# TinyCube11b_Lib.net
KiCad netlist of a schematic drawn in EAGLE
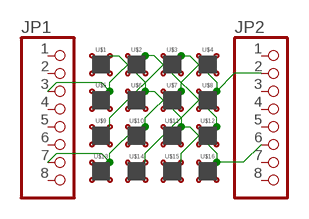
[diagram p0: schematic, sheet 1]

(export (version "E")
  (design (tool "Eeschema 10.0.6"))
  (components
    (comp (ref "JP1")
      (value "PINHD-1X8BIG")
      (footprint "eagle-import:1X08-BIG")
      (libsource (lib "eagle-import") (part "PINHD-1X8BIG"))
    )
    (comp (ref "JP2")
      (value "PINHD-1X8BIG")
      (footprint "eagle-import:1X08-BIG")
      (libsource (lib "eagle-import") (part "PINHD-1X8BIG"))
    )
    (comp (ref "U$1")
      (value "PILLAR")
      (footprint "eagle-import:10MIL")
      (libsource (lib "eagle-import") (part "PILLAR"))
    )
    (comp (ref "U$2")
      (value "PILLAR")
      (footprint "eagle-import:10MIL")
      (libsource (lib "eagle-import") (part "PILLAR"))
    )
    (comp (ref "U$3")
      (value "PILLAR")
      (footprint "eagle-import:10MIL")
      (libsource (lib "eagle-import") (part "PILLAR"))
    )
    (comp (ref "U$4")
      (value "PILLAR")
      (footprint "eagle-import:10MIL")
      (libsource (lib "eagle-import") (part "PILLAR"))
    )
    (comp (ref "U$5")
      (value "PILLAR")
      (footprint "eagle-import:10MIL")
      (libsource (lib "eagle-import") (part "PILLAR"))
    )
    (comp (ref "U$6")
      (value "PILLAR")
      (footprint "eagle-import:10MIL")
      (libsource (lib "eagle-import") (part "PILLAR"))
    )
    (comp (ref "U$7")
      (value "PILLAR")
      (footprint "eagle-import:10MIL")
      (libsource (lib "eagle-import") (part "PILLAR"))
    )
    (comp (ref "U$8")
      (value "PILLAR")
      (footprint "eagle-import:10MIL")
      (libsource (lib "eagle-import") (part "PILLAR"))
    )
    (comp (ref "U$9")
      (value "PILLAR")
      (footprint "eagle-import:10MIL")
      (libsource (lib "eagle-import") (part "PILLAR"))
    )
    (comp (ref "U$10")
      (value "PILLAR")
      (footprint "eagle-import:10MIL")
      (libsource (lib "eagle-import") (part "PILLAR"))
    )
    (comp (ref "U$11")
      (value "PILLAR")
      (footprint "eagle-import:10MIL")
      (libsource (lib "eagle-import") (part "PILLAR"))
    )
    (comp (ref "U$12")
      (value "PILLAR")
      (footprint "eagle-import:10MIL")
      (libsource (lib "eagle-import") (part "PILLAR"))
    )
    (comp (ref "U$13")
      (value "PILLAR")
      (footprint "eagle-import:10MIL")
      (libsource (lib "eagle-import") (part "PILLAR"))
    )
    (comp (ref "U$14")
      (value "PILLAR")
      (footprint "eagle-import:10MIL")
      (libsource (lib "eagle-import") (part "PILLAR"))
    )
    (comp (ref "U$15")
      (value "PILLAR")
      (footprint "eagle-import:10MIL")
      (libsource (lib "eagle-import") (part "PILLAR"))
    )
    (comp (ref "U$16")
      (value "PILLAR")
      (footprint "eagle-import:10MIL")
      (libsource (lib "eagle-import") (part "PILLAR"))
    )
  )
  (nets
    (net (code "1") (name "Net-(U$1-G)") (class "Default")
      (node (ref "JP2") (pin "6") (pinfunction "6_6") (pintype "passive"))
      (node (ref "U$1") (pin "+") (pinfunction "G_+") (pintype "bidirectional"))
      (node (ref "U$11") (pin "+") (pinfunction "G_+") (pintype "bidirectional"))
      (node (ref "U$16") (pin "+") (pinfunction "G_+") (pintype "bidirectional"))
      (node (ref "U$6") (pin "+") (pinfunction "G_+") (pintype "bidirectional"))
    )
    (net (code "2") (name "Net-(U$10-G)") (class "Default")
      (node (ref "JP1") (pin "7") (pinfunction "7_7") (pintype "passive"))
      (node (ref "U$10") (pin "+") (pinfunction "G_+") (pintype "bidirectional"))
      (node (ref "U$13") (pin "+") (pinfunction "G_+") (pintype "bidirectional"))
      (node (ref "U$4") (pin "+") (pinfunction "G_+") (pintype "bidirectional"))
      (node (ref "U$7") (pin "+") (pinfunction "G_+") (pintype "bidirectional"))
    )
    (net (code "3") (name "Net-(U$12-G)") (class "Default")
      (node (ref "JP1") (pin "3") (pinfunction "3_3") (pintype "passive"))
      (node (ref "U$12") (pin "+") (pinfunction "G_+") (pintype "bidirectional"))
      (node (ref "U$15") (pin "+") (pinfunction "G_+") (pintype "bidirectional"))
      (node (ref "U$2") (pin "+") (pinfunction "G_+") (pintype "bidirectional"))
      (node (ref "U$5") (pin "+") (pinfunction "G_+") (pintype "bidirectional"))
    )
    (net (code "4") (name "Net-(U$14-G)") (class "Default")
      (node (ref "JP2") (pin "2") (pinfunction "2_2") (pintype "passive"))
      (node (ref "U$14") (pin "+") (pinfunction "G_+") (pintype "bidirectional"))
      (node (ref "U$3") (pin "+") (pinfunction "G_+") (pintype "bidirectional"))
      (node (ref "U$8") (pin "+") (pinfunction "G_+") (pintype "bidirectional"))
      (node (ref "U$9") (pin "+") (pinfunction "G_+") (pintype "bidirectional"))
    )
    (net (code "5") (name "unconnected-(JP1-Pad1)") (class "Default")
      (node (ref "JP1") (pin "1") (pinfunction "1_1") (pintype "passive"))
    )
    (net (code "6") (name "unconnected-(JP1-Pad2)") (class "Default")
      (node (ref "JP1") (pin "2") (pinfunction "2_2") (pintype "passive"))
    )
    (net (code "7") (name "unconnected-(JP1-Pad4)") (class "Default")
      (node (ref "JP1") (pin "4") (pinfunction "4_4") (pintype "passive"))
    )
    (net (code "8") (name "unconnected-(JP1-Pad5)") (class "Default")
      (node (ref "JP1") (pin "5") (pinfunction "5_5") (pintype "passive"))
    )
    (net (code "9") (name "unconnected-(JP1-Pad6)") (class "Default")
      (node (ref "JP1") (pin "6") (pinfunction "6_6") (pintype "passive"))
    )
    (net (code "10") (name "unconnected-(JP1-Pad8)") (class "Default")
      (node (ref "JP1") (pin "8") (pinfunction "8_8") (pintype "passive"))
    )
    (net (code "11") (name "unconnected-(JP2-Pad1)") (class "Default")
      (node (ref "JP2") (pin "1") (pinfunction "1_1") (pintype "passive"))
    )
    (net (code "12") (name "unconnected-(JP2-Pad3)") (class "Default")
      (node (ref "JP2") (pin "3") (pinfunction "3_3") (pintype "passive"))
    )
    (net (code "13") (name "unconnected-(JP2-Pad4)") (class "Default")
      (node (ref "JP2") (pin "4") (pinfunction "4_4") (pintype "passive"))
    )
    (net (code "14") (name "unconnected-(JP2-Pad5)") (class "Default")
      (node (ref "JP2") (pin "5") (pinfunction "5_5") (pintype "passive"))
    )
    (net (code "15") (name "unconnected-(JP2-Pad7)") (class "Default")
      (node (ref "JP2") (pin "7") (pinfunction "7_7") (pintype "passive"))
    )
    (net (code "16") (name "unconnected-(JP2-Pad8)") (class "Default")
      (node (ref "JP2") (pin "8") (pinfunction "8_8") (pintype "passive"))
    )
    (net (code "17") (name "unconnected-(U$1-A-PadG)") (class "Default")
      (node (ref "U$1") (pin "G") (pinfunction "A_G") (pintype "bidirectional"))
    )
    (net (code "18") (name "unconnected-(U$1-B-PadR)") (class "Default")
      (node (ref "U$1") (pin "R") (pinfunction "B_R") (pintype "bidirectional"))
    )
    (net (code "19") (name "unconnected-(U$1-R-PadB)") (class "Default")
      (node (ref "U$1") (pin "B") (pinfunction "R_B") (pintype "bidirectional"))
    )
    (net (code "20") (name "unconnected-(U$2-A-PadG)") (class "Default")
      (node (ref "U$2") (pin "G") (pinfunction "A_G") (pintype "bidirectional"))
    )
    (net (code "21") (name "unconnected-(U$2-B-PadR)") (class "Default")
      (node (ref "U$2") (pin "R") (pinfunction "B_R") (pintype "bidirectional"))
    )
    (net (code "22") (name "unconnected-(U$2-R-PadB)") (class "Default")
      (node (ref "U$2") (pin "B") (pinfunction "R_B") (pintype "bidirectional"))
    )
    (net (code "23") (name "unconnected-(U$3-A-PadG)") (class "Default")
      (node (ref "U$3") (pin "G") (pinfunction "A_G") (pintype "bidirectional"))
    )
    (net (code "24") (name "unconnected-(U$3-B-PadR)") (class "Default")
      (node (ref "U$3") (pin "R") (pinfunction "B_R") (pintype "bidirectional"))
    )
    (net (code "25") (name "unconnected-(U$3-R-PadB)") (class "Default")
      (node (ref "U$3") (pin "B") (pinfunction "R_B") (pintype "bidirectional"))
    )
    (net (code "26") (name "unconnected-(U$4-A-PadG)") (class "Default")
      (node (ref "U$4") (pin "G") (pinfunction "A_G") (pintype "bidirectional"))
    )
    (net (code "27") (name "unconnected-(U$4-B-PadR)") (class "Default")
      (node (ref "U$4") (pin "R") (pinfunction "B_R") (pintype "bidirectional"))
    )
    (net (code "28") (name "unconnected-(U$4-R-PadB)") (class "Default")
      (node (ref "U$4") (pin "B") (pinfunction "R_B") (pintype "bidirectional"))
    )
    (net (code "29") (name "unconnected-(U$5-A-PadG)") (class "Default")
      (node (ref "U$5") (pin "G") (pinfunction "A_G") (pintype "bidirectional"))
    )
    (net (code "30") (name "unconnected-(U$5-B-PadR)") (class "Default")
      (node (ref "U$5") (pin "R") (pinfunction "B_R") (pintype "bidirectional"))
    )
    (net (code "31") (name "unconnected-(U$5-R-PadB)") (class "Default")
      (node (ref "U$5") (pin "B") (pinfunction "R_B") (pintype "bidirectional"))
    )
    (net (code "32") (name "unconnected-(U$6-A-PadG)") (class "Default")
      (node (ref "U$6") (pin "G") (pinfunction "A_G") (pintype "bidirectional"))
    )
    (net (code "33") (name "unconnected-(U$6-B-PadR)") (class "Default")
      (node (ref "U$6") (pin "R") (pinfunction "B_R") (pintype "bidirectional"))
    )
    (net (code "34") (name "unconnected-(U$6-R-PadB)") (class "Default")
      (node (ref "U$6") (pin "B") (pinfunction "R_B") (pintype "bidirectional"))
    )
    (net (code "35") (name "unconnected-(U$7-A-PadG)") (class "Default")
      (node (ref "U$7") (pin "G") (pinfunction "A_G") (pintype "bidirectional"))
    )
    (net (code "36") (name "unconnected-(U$7-B-PadR)") (class "Default")
      (node (ref "U$7") (pin "R") (pinfunction "B_R") (pintype "bidirectional"))
    )
    (net (code "37") (name "unconnected-(U$7-R-PadB)") (class "Default")
      (node (ref "U$7") (pin "B") (pinfunction "R_B") (pintype "bidirectional"))
    )
    (net (code "38") (name "unconnected-(U$8-A-PadG)") (class "Default")
      (node (ref "U$8") (pin "G") (pinfunction "A_G") (pintype "bidirectional"))
    )
    (net (code "39") (name "unconnected-(U$8-B-PadR)") (class "Default")
      (node (ref "U$8") (pin "R") (pinfunction "B_R") (pintype "bidirectional"))
    )
    (net (code "40") (name "unconnected-(U$8-R-PadB)") (class "Default")
      (node (ref "U$8") (pin "B") (pinfunction "R_B") (pintype "bidirectional"))
    )
    (net (code "41") (name "unconnected-(U$9-A-PadG)") (class "Default")
      (node (ref "U$9") (pin "G") (pinfunction "A_G") (pintype "bidirectional"))
    )
    (net (code "42") (name "unconnected-(U$9-B-PadR)") (class "Default")
      (node (ref "U$9") (pin "R") (pinfunction "B_R") (pintype "bidirectional"))
    )
    (net (code "43") (name "unconnected-(U$9-R-PadB)") (class "Default")
      (node (ref "U$9") (pin "B") (pinfunction "R_B") (pintype "bidirectional"))
    )
    (net (code "44") (name "unconnected-(U$10-A-PadG)") (class "Default")
      (node (ref "U$10") (pin "G") (pinfunction "A_G") (pintype "bidirectional"))
    )
    (net (code "45") (name "unconnected-(U$10-B-PadR)") (class "Default")
      (node (ref "U$10") (pin "R") (pinfunction "B_R") (pintype "bidirectional"))
    )
    (net (code "46") (name "unconnected-(U$10-R-PadB)") (class "Default")
      (node (ref "U$10") (pin "B") (pinfunction "R_B") (pintype "bidirectional"))
    )
    (net (code "47") (name "unconnected-(U$11-A-PadG)") (class "Default")
      (node (ref "U$11") (pin "G") (pinfunction "A_G") (pintype "bidirectional"))
    )
    (net (code "48") (name "unconnected-(U$11-B-PadR)") (class "Default")
      (node (ref "U$11") (pin "R") (pinfunction "B_R") (pintype "bidirectional"))
    )
    (net (code "49") (name "unconnected-(U$11-R-PadB)") (class "Default")
      (node (ref "U$11") (pin "B") (pinfunction "R_B") (pintype "bidirectional"))
    )
    (net (code "50") (name "unconnected-(U$12-A-PadG)") (class "Default")
      (node (ref "U$12") (pin "G") (pinfunction "A_G") (pintype "bidirectional"))
    )
    (net (code "51") (name "unconnected-(U$12-B-PadR)") (class "Default")
      (node (ref "U$12") (pin "R") (pinfunction "B_R") (pintype "bidirectional"))
    )
    (net (code "52") (name "unconnected-(U$12-R-PadB)") (class "Default")
      (node (ref "U$12") (pin "B") (pinfunction "R_B") (pintype "bidirectional"))
    )
    (net (code "53") (name "unconnected-(U$13-A-PadG)") (class "Default")
      (node (ref "U$13") (pin "G") (pinfunction "A_G") (pintype "bidirectional"))
    )
    (net (code "54") (name "unconnected-(U$13-B-PadR)") (class "Default")
      (node (ref "U$13") (pin "R") (pinfunction "B_R") (pintype "bidirectional"))
    )
    (net (code "55") (name "unconnected-(U$13-R-PadB)") (class "Default")
      (node (ref "U$13") (pin "B") (pinfunction "R_B") (pintype "bidirectional"))
    )
    (net (code "56") (name "unconnected-(U$14-A-PadG)") (class "Default")
      (node (ref "U$14") (pin "G") (pinfunction "A_G") (pintype "bidirectional"))
    )
    (net (code "57") (name "unconnected-(U$14-B-PadR)") (class "Default")
      (node (ref "U$14") (pin "R") (pinfunction "B_R") (pintype "bidirectional"))
    )
    (net (code "58") (name "unconnected-(U$14-R-PadB)") (class "Default")
      (node (ref "U$14") (pin "B") (pinfunction "R_B") (pintype "bidirectional"))
    )
    (net (code "59") (name "unconnected-(U$15-A-PadG)") (class "Default")
      (node (ref "U$15") (pin "G") (pinfunction "A_G") (pintype "bidirectional"))
    )
    (net (code "60") (name "unconnected-(U$15-B-PadR)") (class "Default")
      (node (ref "U$15") (pin "R") (pinfunction "B_R") (pintype "bidirectional"))
    )
    (net (code "61") (name "unconnected-(U$15-R-PadB)") (class "Default")
      (node (ref "U$15") (pin "B") (pinfunction "R_B") (pintype "bidirectional"))
    )
    (net (code "62") (name "unconnected-(U$16-A-PadG)") (class "Default")
      (node (ref "U$16") (pin "G") (pinfunction "A_G") (pintype "bidirectional"))
    )
    (net (code "63") (name "unconnected-(U$16-B-PadR)") (class "Default")
      (node (ref "U$16") (pin "R") (pinfunction "B_R") (pintype "bidirectional"))
    )
    (net (code "64") (name "unconnected-(U$16-R-PadB)") (class "Default")
      (node (ref "U$16") (pin "B") (pinfunction "R_B") (pintype "bidirectional"))
    )
  )
)
